# Schematics.net
KiCad netlist of a schematic drawn in EAGLE
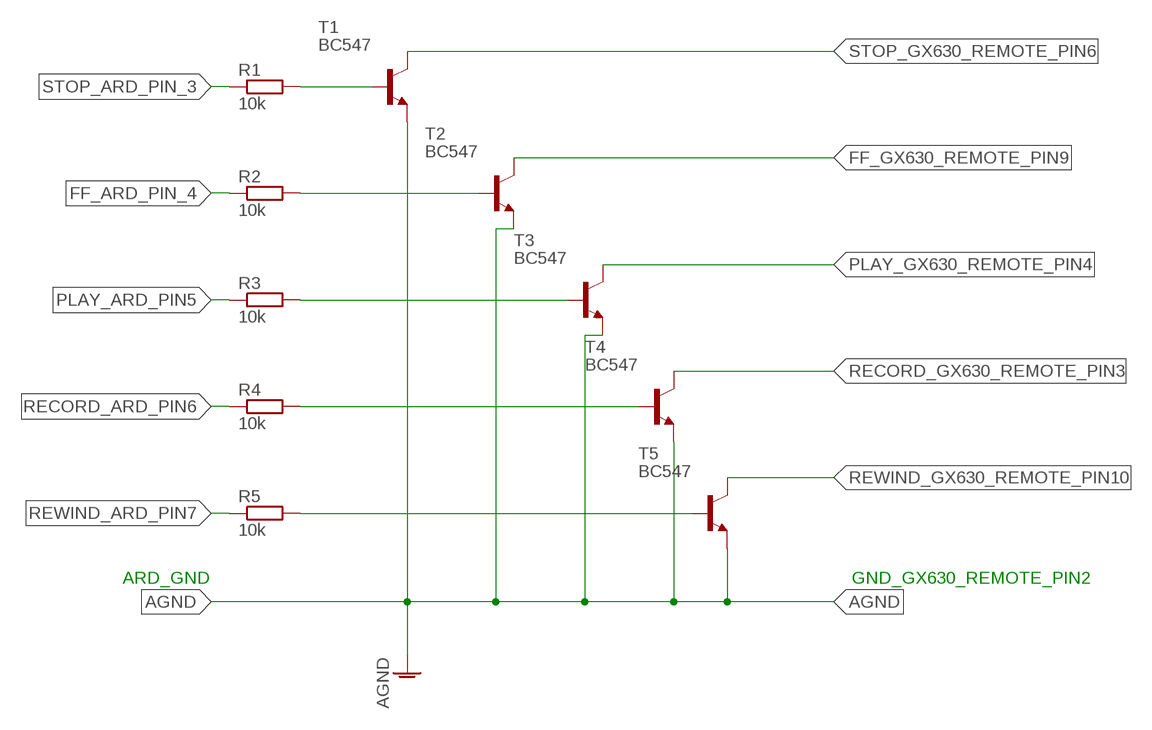
[diagram p0: schematic, sheet 1]

(export (version "E")
  (design (tool "Eeschema 10.0.6"))
  (components
    (comp (ref "R1")
      (value "10k")
      (footprint "eagle-import:0207_10")
      (libsource (lib "eagle-import") (part "R-EU_0207/10"))
    )
    (comp (ref "R2")
      (value "10k")
      (footprint "eagle-import:0207_10")
      (libsource (lib "eagle-import") (part "R-EU_0207/10"))
    )
    (comp (ref "R3")
      (value "10k")
      (footprint "eagle-import:0207_10")
      (libsource (lib "eagle-import") (part "R-EU_0207/10"))
    )
    (comp (ref "R4")
      (value "10k")
      (footprint "eagle-import:0207_10")
      (libsource (lib "eagle-import") (part "R-EU_0207/10"))
    )
    (comp (ref "R5")
      (value "10k")
      (footprint "eagle-import:0207_10")
      (libsource (lib "eagle-import") (part "R-EU_0207/10"))
    )
    (comp (ref "T1")
      (value "BC547")
      (footprint "eagle-import:TO92")
      (libsource (lib "eagle-import") (part "BC547"))
    )
    (comp (ref "T2")
      (value "BC547")
      (footprint "eagle-import:TO92")
      (libsource (lib "eagle-import") (part "BC547"))
    )
    (comp (ref "T3")
      (value "BC547")
      (footprint "eagle-import:TO92")
      (libsource (lib "eagle-import") (part "BC547"))
    )
    (comp (ref "T4")
      (value "BC547")
      (footprint "eagle-import:TO92")
      (libsource (lib "eagle-import") (part "BC547"))
    )
    (comp (ref "T5")
      (value "BC547")
      (footprint "eagle-import:TO92")
      (libsource (lib "eagle-import") (part "BC547"))
    )
  )
  (nets
    (net (code "1") (name "AGND") (class "Default")
      (node (ref "T1") (pin "1") (pinfunction "E_1") (pintype "passive"))
      (node (ref "T2") (pin "1") (pinfunction "E_1") (pintype "passive"))
      (node (ref "T3") (pin "1") (pinfunction "E_1") (pintype "passive"))
      (node (ref "T4") (pin "1") (pinfunction "E_1") (pintype "passive"))
      (node (ref "T5") (pin "1") (pinfunction "E_1") (pintype "passive"))
    )
    (net (code "2") (name "FF_ARD_PIN_4") (class "Default")
      (node (ref "R2") (pin "1") (pinfunction "1_1") (pintype "passive"))
    )
    (net (code "3") (name "FF_GX630_REMOTE_PIN9") (class "Default")
      (node (ref "T2") (pin "3") (pinfunction "C_3") (pintype "passive"))
    )
    (net (code "4") (name "Net-(T1-B)") (class "Default")
      (node (ref "R1") (pin "2") (pinfunction "2_2") (pintype "passive"))
      (node (ref "T1") (pin "2") (pinfunction "B_2") (pintype "passive"))
    )
    (net (code "5") (name "Net-(T2-B)") (class "Default")
      (node (ref "R2") (pin "2") (pinfunction "2_2") (pintype "passive"))
      (node (ref "T2") (pin "2") (pinfunction "B_2") (pintype "passive"))
    )
    (net (code "6") (name "Net-(T3-B)") (class "Default")
      (node (ref "R3") (pin "2") (pinfunction "2_2") (pintype "passive"))
      (node (ref "T3") (pin "2") (pinfunction "B_2") (pintype "passive"))
    )
    (net (code "7") (name "Net-(T4-B)") (class "Default")
      (node (ref "R4") (pin "2") (pinfunction "2_2") (pintype "passive"))
      (node (ref "T4") (pin "2") (pinfunction "B_2") (pintype "passive"))
    )
    (net (code "8") (name "Net-(T5-B)") (class "Default")
      (node (ref "R5") (pin "2") (pinfunction "2_2") (pintype "passive"))
      (node (ref "T5") (pin "2") (pinfunction "B_2") (pintype "passive"))
    )
    (net (code "9") (name "PLAY_ARD_PIN5") (class "Default")
      (node (ref "R3") (pin "1") (pinfunction "1_1") (pintype "passive"))
    )
    (net (code "10") (name "PLAY_GX630_REMOTE_PIN4") (class "Default")
      (node (ref "T3") (pin "3") (pinfunction "C_3") (pintype "passive"))
    )
    (net (code "11") (name "RECORD_ARD_PIN6") (class "Default")
      (node (ref "R4") (pin "1") (pinfunction "1_1") (pintype "passive"))
    )
    (net (code "12") (name "RECORD_GX630_REMOTE_PIN3") (class "Default")
      (node (ref "T4") (pin "3") (pinfunction "C_3") (pintype "passive"))
    )
    (net (code "13") (name "REWIND_ARD_PIN7") (class "Default")
      (node (ref "R5") (pin "1") (pinfunction "1_1") (pintype "passive"))
    )
    (net (code "14") (name "REWIND_GX630_REMOTE_PIN10") (class "Default")
      (node (ref "T5") (pin "3") (pinfunction "C_3") (pintype "passive"))
    )
    (net (code "15") (name "STOP_ARD_PIN_3") (class "Default")
      (node (ref "R1") (pin "1") (pinfunction "1_1") (pintype "passive"))
    )
    (net (code "16") (name "STOP_GX630_REMOTE_PIN6") (class "Default")
      (node (ref "T1") (pin "3") (pinfunction "C_3") (pintype "passive"))
    )
  )
)
